# Stepdown_5V_1A.net
KiCad netlist of a schematic drawn in Altium Designer
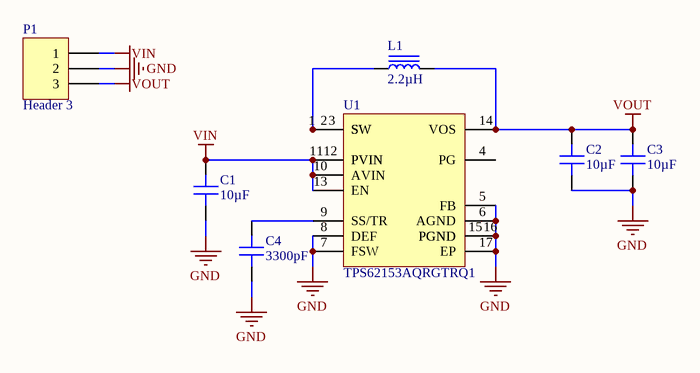
[diagram p0: Stepdown 5V 1A.SchDoc]

(export (version "E")
  (design (tool "Eeschema 10.0.6"))
  (components
    (comp (ref "C1")
      (value "10µF")
      (footprint "CAP 0805_2012")
      (description "CAP CER 10UF 25V X5R 0805")
      (fields
        (field (name "PART NUMBER") "C2012X5R1E106K085AC")
        (field (name "MANUFACTURER") "TDK Corporation")
      )
      (libsource (lib "Celestial Altium Library - altium_library") (part "Capacitor"))
    )
    (comp (ref "C2")
      (value "10µF")
      (footprint "CAP 0805_2012")
      (description "CAP CER 10UF 25V X5R 0805")
      (fields
        (field (name "PART NUMBER") "C2012X5R1E106K085AC")
        (field (name "MANUFACTURER") "TDK Corporation")
      )
      (libsource (lib "Celestial Altium Library - altium_library") (part "Capacitor"))
    )
    (comp (ref "C3")
      (value "10µF")
      (footprint "CAP 0805_2012")
      (description "CAP CER 10UF 25V X5R 0805")
      (fields
        (field (name "PART NUMBER") "C2012X5R1E106K085AC")
        (field (name "MANUFACTURER") "TDK Corporation")
      )
      (libsource (lib "Celestial Altium Library - altium_library") (part "Capacitor"))
    )
    (comp (ref "C4")
      (value "3300pF")
      (footprint "CAP 0603_1608")
      (description "CAP CER 3300PF 100V X7R 0603")
      (fields (field (name "PART NUMBER") "06031C332K4T2A") (field (name "MANUFACTURER") "AVX Corporation"))
      (libsource (lib "Celestial Altium Library - altium_library") (part "Capacitor"))
    )
    (comp (ref "L1")
      (value "2.2µH")
      (footprint "IND 0806_2016")
      (description "FIXED IND 2.2UH 1.8A 117MOHM")
      (fields
        (field (name "PART NUMBER") "CIGW201610GH2R2MLE")
        (field (name "MANUFACTURER") "Samsung Electro-Mechanics")
      )
      (libsource (lib "Celestial Altium Library - altium_library") (part "Inductor"))
    )
    (comp (ref "P1")
      (value "Header 3")
      (footprint "HDR1X3")
      (description "Header, 3-Pin")
      (fields (field (name "PUBLISHER") "Altium Limited"))
      (libsource (lib "Miscellaneous Connectors") (part "Header 3"))
    )
    (comp (ref "U1")
      (value "TPS62153AQRGTRQ1")
      (footprint "16-VFQFN Exposed Pad")
      (description "Buck Switching Regulator IC Positive Fixed 5V 1 Output 1A 16-VFQFN Exposed Pad")
      (fields (field (name "MF") "Texas Instruments"))
      (libsource (lib "Proteus") (part "TPS62153AQRGTRQ1"))
    )
  )
  (nets
    (net (code "1") (name "GND") (class "Default")
      (node (ref "C1") (pin "1") (pinfunction "1_1") (pintype "passive"))
      (node (ref "C2") (pin "1") (pinfunction "1_1") (pintype "passive"))
      (node (ref "C3") (pin "1") (pinfunction "1_1") (pintype "passive"))
      (node (ref "C4") (pin "1") (pinfunction "1_1") (pintype "passive"))
      (node (ref "P1") (pin "2") (pinfunction "2_2") (pintype "passive"))
      (node (ref "U1") (pin "15") (pinfunction "PGND_15") (pintype "passive"))
      (node (ref "U1") (pin "16") (pinfunction "PGND_16") (pintype "passive"))
      (node (ref "U1") (pin "17") (pinfunction "EP_17") (pintype "passive"))
      (node (ref "U1") (pin "5") (pinfunction "FB_5") (pintype "passive"))
      (node (ref "U1") (pin "6") (pinfunction "AGND_6") (pintype "passive"))
      (node (ref "U1") (pin "7") (pinfunction "FSW_7") (pintype "passive"))
      (node (ref "U1") (pin "8") (pinfunction "DEF_8") (pintype "passive"))
    )
    (net (code "2") (name "Net-(L1-Pad1)") (class "Default")
      (node (ref "L1") (pin "1") (pinfunction "1_1") (pintype "passive"))
      (node (ref "U1") (pin "1") (pinfunction "SW_1") (pintype "passive"))
      (node (ref "U1") (pin "2") (pinfunction "SW_2") (pintype "passive"))
      (node (ref "U1") (pin "3") (pinfunction "SW_3") (pintype "passive"))
    )
    (net (code "3") (name "Net-(U1-SS{slash}TR)") (class "Default")
      (node (ref "C4") (pin "2") (pinfunction "2_2") (pintype "passive"))
      (node (ref "U1") (pin "9") (pinfunction "SS/TR_9") (pintype "passive"))
    )
    (net (code "4") (name "VIN") (class "Default")
      (node (ref "C1") (pin "2") (pinfunction "2_2") (pintype "passive"))
      (node (ref "P1") (pin "1") (pinfunction "1_1") (pintype "passive"))
      (node (ref "U1") (pin "10") (pinfunction "AVIN_10") (pintype "passive"))
      (node (ref "U1") (pin "11") (pinfunction "PVIN_11") (pintype "passive"))
      (node (ref "U1") (pin "12") (pinfunction "PVIN_12") (pintype "passive"))
      (node (ref "U1") (pin "13") (pinfunction "EN_13") (pintype "passive"))
    )
    (net (code "5") (name "VOUT") (class "Default")
      (node (ref "C2") (pin "2") (pinfunction "2_2") (pintype "passive"))
      (node (ref "C3") (pin "2") (pinfunction "2_2") (pintype "passive"))
      (node (ref "L1") (pin "2") (pinfunction "2_2") (pintype "passive"))
      (node (ref "P1") (pin "3") (pinfunction "3_3") (pintype "passive"))
      (node (ref "U1") (pin "14") (pinfunction "VOS_14") (pintype "passive"))
    )
    (net (code "6") (name "unconnected-(U1-PG-Pad4)") (class "Default")
      (node (ref "U1") (pin "4") (pinfunction "PG_4") (pintype "passive"))
    )
  )
)
